# ETAG_v4.net
KiCad netlist of a schematic drawn in EAGLE
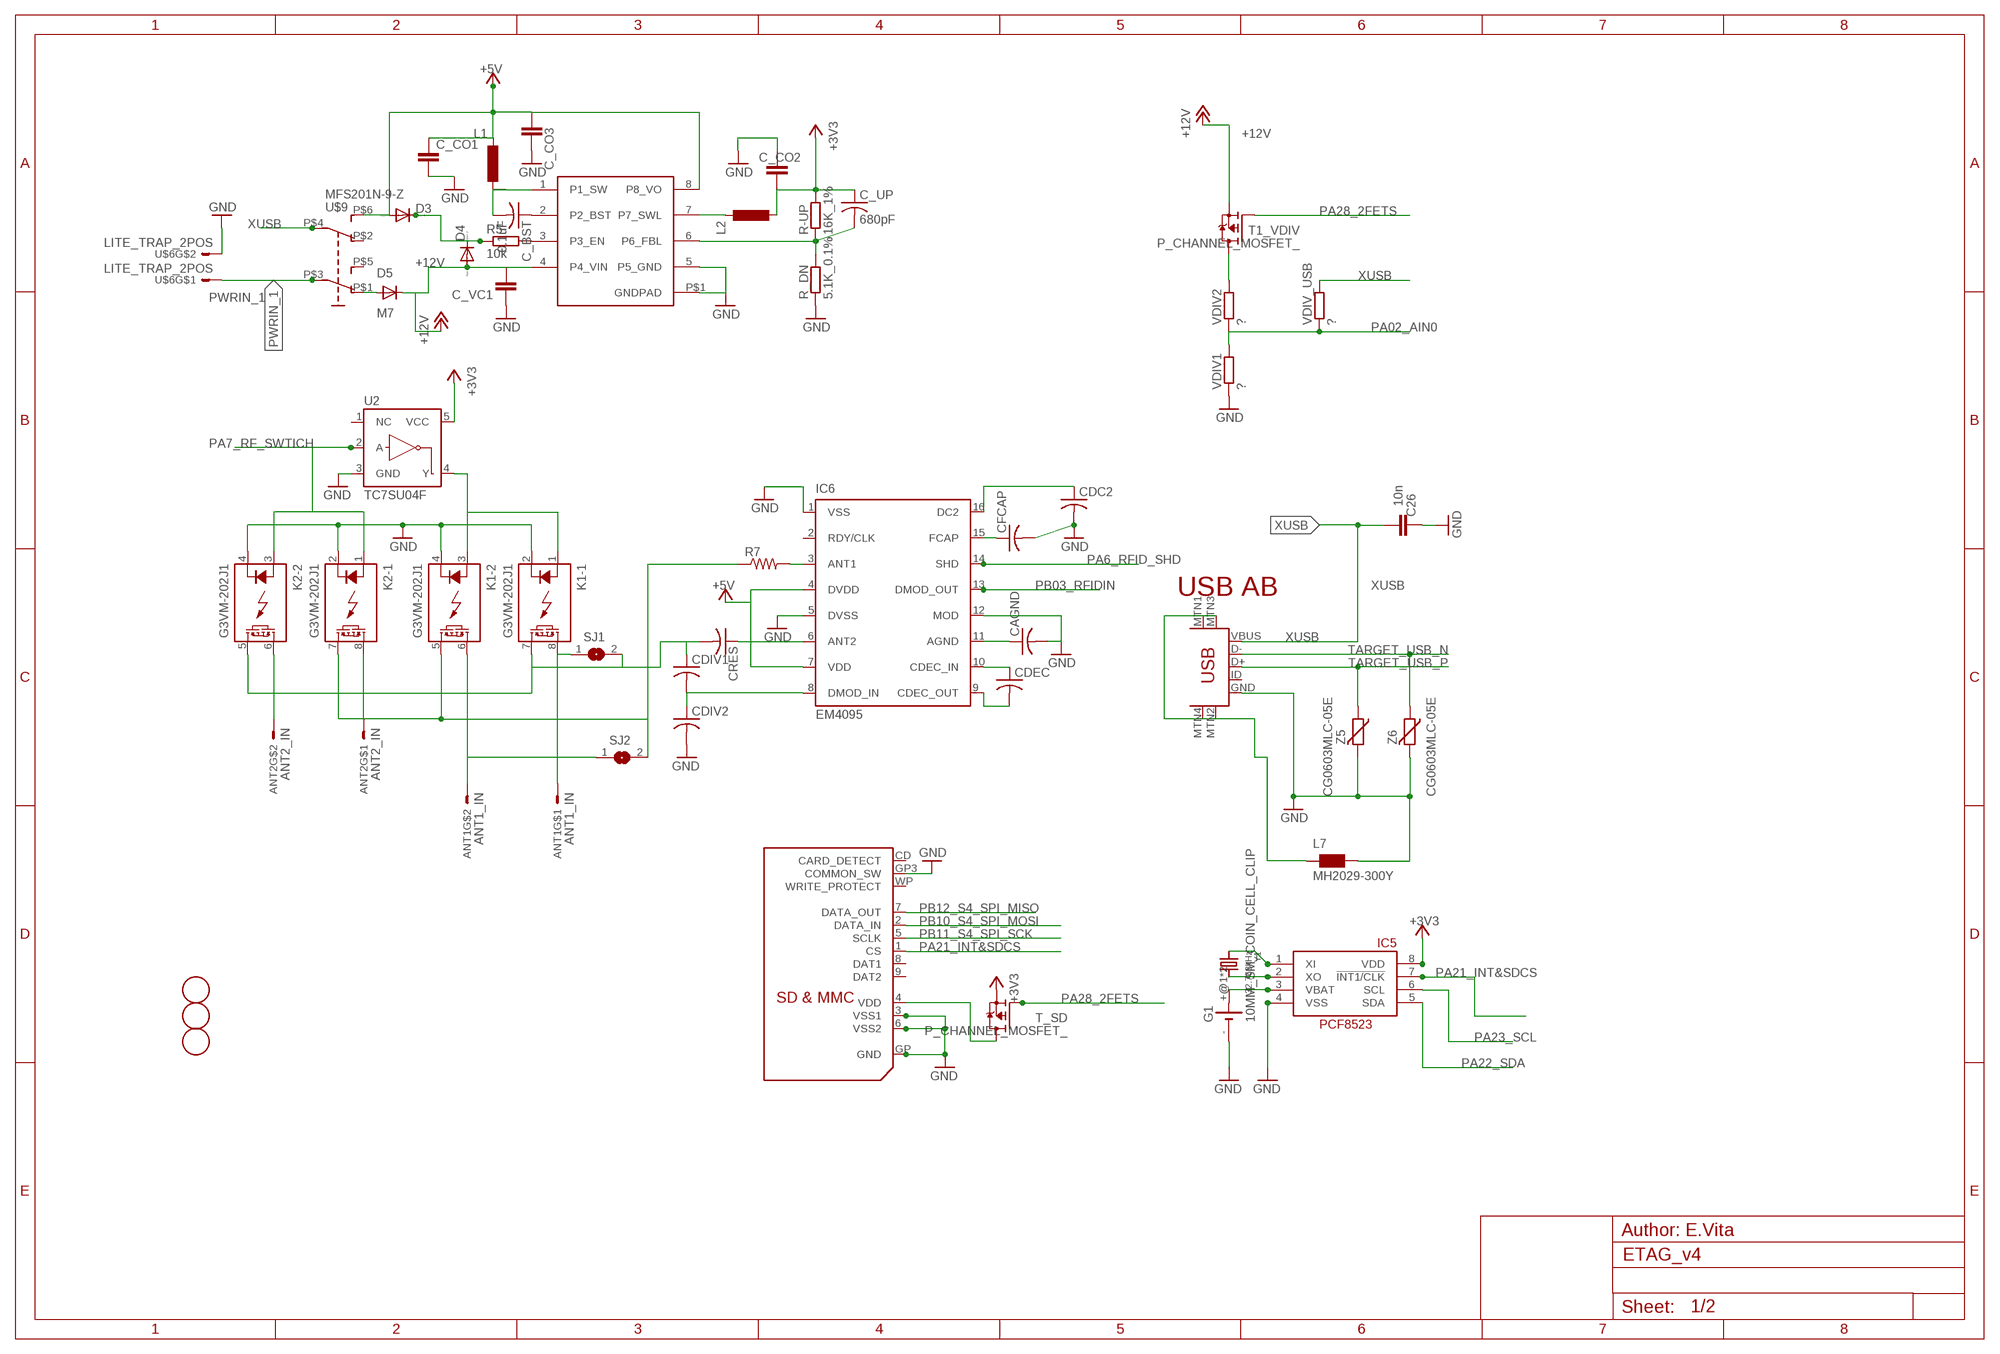
[diagram p0: schematic, sheet 1]
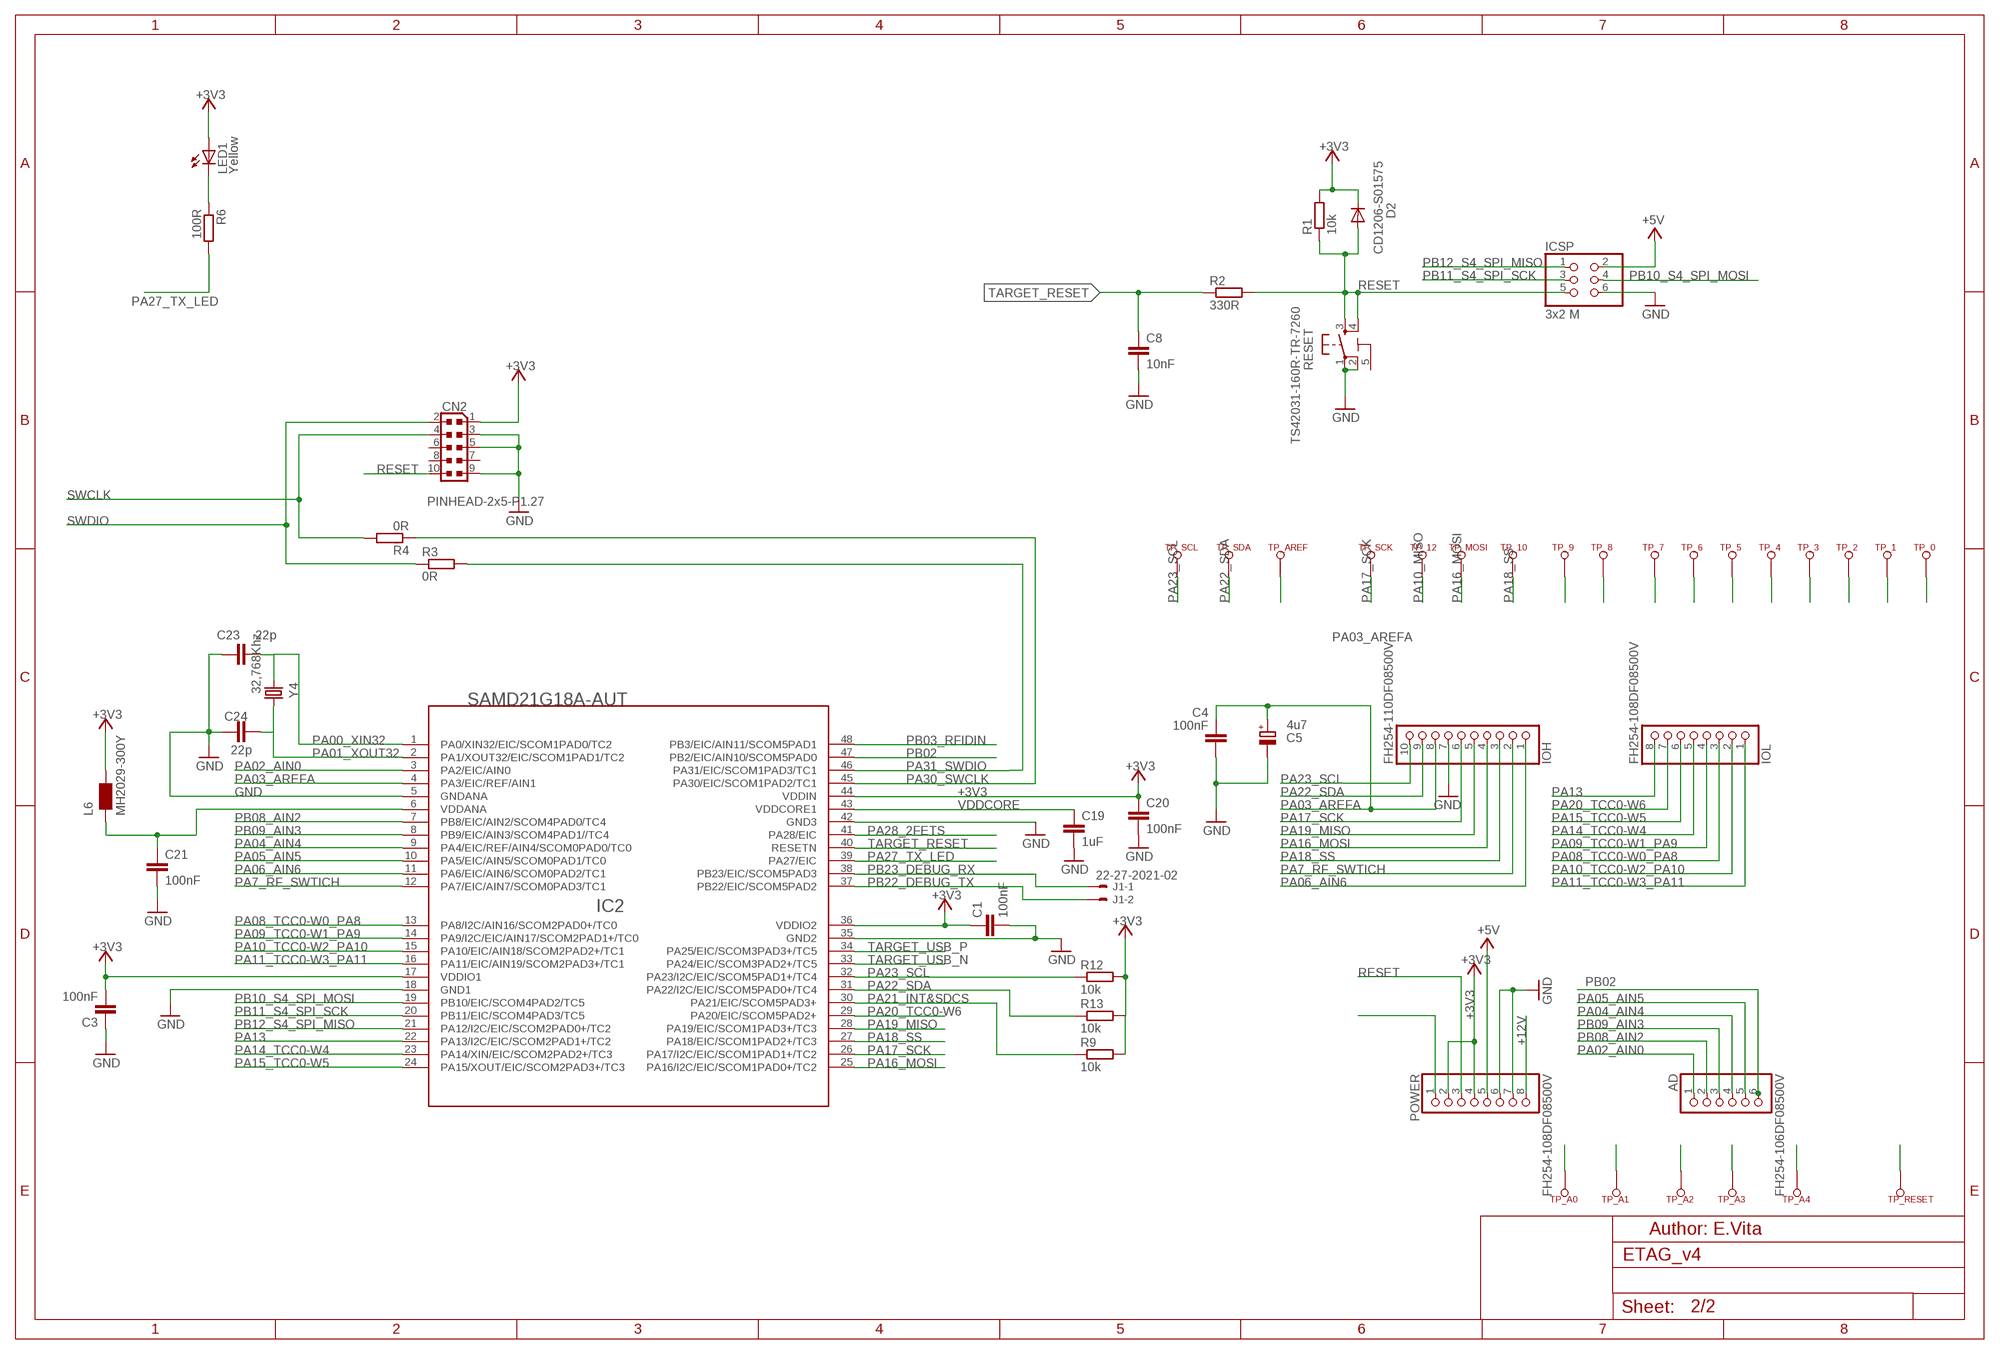
[diagram p1: schematic, sheet 2]

(export (version "E")
  (design (tool "Eeschema 10.0.6"))
  (components
    (comp (ref "AD")
      (value "FH254-106DF08500V")
      (footprint "eagle-import:1X06")
      (fields (field (name "PART_NUMBER") "20TW-535"))
      (libsource (lib "eagle-import") (part "1682_20TW-535_STD"))
    )
    (comp (ref "C1")
      (value "100nF")
      (footprint "eagle-import:C0603-ROUND")
      (fields (field (name "PART_NUMBER") "cl10b104kbnc"))
      (libsource (lib "eagle-import") (part "0015_100NF_0603"))
    )
    (comp (ref "C3")
      (value "100nF")
      (footprint "eagle-import:C0603-ROUND")
      (fields (field (name "PART_NUMBER") "cl10b104kbnc"))
      (libsource (lib "eagle-import") (part "0015_100NF_0603"))
    )
    (comp (ref "C4")
      (value "100nF")
      (footprint "eagle-import:C0603-ROUND")
      (fields (field (name "PART_NUMBER") "cl10b104kbnc"))
      (libsource (lib "eagle-import") (part "0015_100NF_0603"))
    )
    (comp (ref "C5")
      (value "4u7")
      (footprint "eagle-import:SMC_A")
      (fields (field (name "PART_NUMBER") "TAJA475M016RNJ"))
      (libsource (lib "eagle-import") (part "0474_TAJA475M016RNJ"))
    )
    (comp (ref "C8")
      (value "10nF")
      (footprint "eagle-import:C0603-ROUND")
      (fields (field (name "PART_NUMBER") "10nF_0603"))
      (libsource (lib "eagle-import") (part "0142_10NF_0603"))
    )
    (comp (ref "C19")
      (value "1uF")
      (footprint "eagle-import:C0603-ROUND")
      (fields (field (name "PART_NUMBER") "1uF_0603/GRM188R61E105KA12D"))
      (libsource (lib "eagle-import") (part "0006_1UF_0603/GRM188R61E105KA12D"))
    )
    (comp (ref "C20")
      (value "100nF")
      (footprint "eagle-import:C0603-ROUND")
      (fields (field (name "PART_NUMBER") "cl10b104kbnc"))
      (libsource (lib "eagle-import") (part "0015_100NF_0603"))
    )
    (comp (ref "C21")
      (value "100nF")
      (footprint "eagle-import:C0603-ROUND")
      (fields (field (name "PART_NUMBER") "cl10b104kbnc"))
      (libsource (lib "eagle-import") (part "0015_100NF_0603"))
    )
    (comp (ref "C23")
      (value "22p")
      (footprint "eagle-import:C0603-ROUND")
      (fields (field (name "PART_NUMBER") "22pF_0603"))
      (libsource (lib "eagle-import") (part "0014_22PF_0603"))
    )
    (comp (ref "C24")
      (value "22p")
      (footprint "eagle-import:C0603-ROUND")
      (fields (field (name "PART_NUMBER") "22pF_0603"))
      (libsource (lib "eagle-import") (part "0014_22PF_0603"))
    )
    (comp (ref "CN2")
      (value "PINHEAD-2x5-P1.27")
      (footprint "eagle-import:PINHEAD_2X05_127")
      (libsource (lib "eagle-import") (part "0171_PH127-205DF055G00AROUND-PADS"))
    )
    (comp (ref "D2")
      (value "CD1206-S01575")
      (footprint "eagle-import:MINIMELF")
      (libsource (lib "eagle-import") (part "0012_CD1206-S01575"))
    )
    (comp (ref "IC2")
      (value "SAMD21G18A-AUT")
      (footprint "eagle-import:TQFP48-7X7")
      (libsource (lib "eagle-import") (part "1792_SAMD21G18A-AUT"))
    )
    (comp (ref "ICSP")
      (value "3x2 M")
      (footprint "eagle-import:2X03")
      (fields (field (name "PART_NUMBER") "PH254-203DF118A00V"))
      (libsource (lib "eagle-import") (part "0114_PH254-203DF118A00V"))
    )
    (comp (ref "IOH")
      (value "FH254-110DF08500V")
      (footprint "eagle-import:1X10")
      (fields (field (name "PART_NUMBER") "20TW-537"))
      (libsource (lib "eagle-import") (part "1684_20TW-537"))
    )
    (comp (ref "IOL")
      (value "FH254-108DF08500V")
      (footprint "eagle-import:1X08")
      (fields (field (name "PART_NUMBER") "20TW-536"))
      (libsource (lib "eagle-import") (part "1683_20TW-536"))
    )
    (comp (ref "J1")
      (value "22-27-2021-02")
      (footprint "eagle-import:6410-02")
      (libsource (lib "eagle-import") (part "22-?-0227-2021"))
    )
    (comp (ref "L6")
      (value "MH2029-300Y")
      (footprint "eagle-import:0805")
      (fields (field (name "PART_NUMBER") "BLM21PG300SN1D_/_MH2029-300Y"))
      (libsource (lib "eagle-import") (part "0001_BLM21PG300SN1D_/_MH2029-300Y"))
    )
    (comp (ref "LED1")
      (value "Yellow")
      (footprint "eagle-import:CHIPLED_0805")
      (fields (field (name "PART_NUMBER") "KPT-2012YC"))
      (libsource (lib "eagle-import") (part "0044_KPT-2012YC"))
    )
    (comp (ref "POWER")
      (value "FH254-108DF08500V")
      (footprint "eagle-import:1X08")
      (fields (field (name "PART_NUMBER") "20TW-536"))
      (libsource (lib "eagle-import") (part "1683_20TW-536"))
    )
    (comp (ref "R1")
      (value "10k")
      (footprint "eagle-import:R0603-ROUND")
      (fields (field (name "PART_NUMBER") "CR0603JW103L"))
      (libsource (lib "eagle-import") (part "0028_CR0603JW103L"))
    )
    (comp (ref "R2")
      (value "330R")
      (footprint "eagle-import:R0603-ROUND")
      (fields (field (name "PART_NUMBER") "330R_0603"))
      (libsource (lib "eagle-import") (part "0049_330R_0603"))
    )
    (comp (ref "R3")
      (value "0R")
      (footprint "eagle-import:R0603-ROUND")
      (fields (field (name "PART_NUMBER") "0R_0603"))
      (libsource (lib "eagle-import") (part "0233_0R_0603"))
    )
    (comp (ref "R4")
      (value "0R")
      (footprint "eagle-import:R0603-ROUND")
      (fields (field (name "PART_NUMBER") "0R_0603"))
      (libsource (lib "eagle-import") (part "0233_0R_0603"))
    )
    (comp (ref "R6")
      (value "100R")
      (footprint "eagle-import:R0603-ROUND")
      (fields (field (name "PART_NUMBER") "0R_0603"))
      (libsource (lib "eagle-import") (part "0233_0R_0603"))
    )
    (comp (ref "R9")
      (value "10k")
      (footprint "eagle-import:R0603-ROUND")
      (fields (field (name "PART_NUMBER") "CR0603JW103L"))
      (libsource (lib "eagle-import") (part "0028_CR0603JW103L"))
    )
    (comp (ref "R12")
      (value "10k")
      (footprint "eagle-import:R0603-ROUND")
      (fields (field (name "PART_NUMBER") "CR0603JW103L"))
      (libsource (lib "eagle-import") (part "0028_CR0603JW103L"))
    )
    (comp (ref "R13")
      (value "10k")
      (footprint "eagle-import:R0603-ROUND")
      (fields (field (name "PART_NUMBER") "CR0603JW103L"))
      (libsource (lib "eagle-import") (part "0028_CR0603JW103L"))
    )
    (comp (ref "RESET")
      (value "TS42031-160R-TR-7260")
      (footprint "eagle-import:TS42")
      (fields (field (name "PART_NUMBER") "IT-1157AHNP-160G-G_GTR"))
      (libsource (lib "eagle-import") (part "0946_TS42031-160W-TR-7260"))
    )
    (comp (ref "TP_0")
      (value "TP_SP")
      (footprint "eagle-import:TP-SP")
      (libsource (lib "eagle-import") (part "TP_SP"))
    )
    (comp (ref "TP_1")
      (value "TP_SP")
      (footprint "eagle-import:TP-SP")
      (libsource (lib "eagle-import") (part "TP_SP"))
    )
    (comp (ref "TP_2")
      (value "TP_SP")
      (footprint "eagle-import:TP-SP")
      (libsource (lib "eagle-import") (part "TP_SP"))
    )
    (comp (ref "TP_3")
      (value "TP_SP")
      (footprint "eagle-import:TP-SP")
      (libsource (lib "eagle-import") (part "TP_SP"))
    )
    (comp (ref "TP_4")
      (value "TP_SP")
      (footprint "eagle-import:TP-SP")
      (libsource (lib "eagle-import") (part "TP_SP"))
    )
    (comp (ref "TP_5")
      (value "TP_SP")
      (footprint "eagle-import:TP-SP")
      (libsource (lib "eagle-import") (part "TP_SP"))
    )
    (comp (ref "TP_6")
      (value "TP_SP")
      (footprint "eagle-import:TP-SP")
      (libsource (lib "eagle-import") (part "TP_SP"))
    )
    (comp (ref "TP_7")
      (value "TP_SP")
      (footprint "eagle-import:TP-SP")
      (libsource (lib "eagle-import") (part "TP_SP"))
    )
    (comp (ref "TP_8")
      (value "TP_SP")
      (footprint "eagle-import:TP-SP")
      (libsource (lib "eagle-import") (part "TP_SP"))
    )
    (comp (ref "TP_9")
      (value "TP_SP")
      (footprint "eagle-import:TP-SP")
      (libsource (lib "eagle-import") (part "TP_SP"))
    )
    (comp (ref "TP_10")
      (value "TP_SP")
      (footprint "eagle-import:TP-SP")
      (libsource (lib "eagle-import") (part "TP_SP"))
    )
    (comp (ref "TP_12")
      (value "TP_SP")
      (footprint "eagle-import:TP-SP")
      (libsource (lib "eagle-import") (part "TP_SP"))
    )
    (comp (ref "TP_A0")
      (value "TP_SP")
      (footprint "eagle-import:TP-SP")
      (libsource (lib "eagle-import") (part "TP_SP"))
    )
    (comp (ref "TP_A1")
      (value "TP_SP")
      (footprint "eagle-import:TP-SP")
      (libsource (lib "eagle-import") (part "TP_SP"))
    )
    (comp (ref "TP_A2")
      (value "TP_SP")
      (footprint "eagle-import:TP-SP")
      (libsource (lib "eagle-import") (part "TP_SP"))
    )
    (comp (ref "TP_A3")
      (value "TP_SP")
      (footprint "eagle-import:TP-SP")
      (libsource (lib "eagle-import") (part "TP_SP"))
    )
    (comp (ref "TP_A4")
      (value "TP_SP")
      (footprint "eagle-import:TP-SP")
      (libsource (lib "eagle-import") (part "TP_SP"))
    )
    (comp (ref "TP_AREF")
      (value "TP_SP")
      (footprint "eagle-import:TP-SP")
      (libsource (lib "eagle-import") (part "TP_SP"))
    )
    (comp (ref "TP_MOSI")
      (value "TP_SP")
      (footprint "eagle-import:TP-SP")
      (libsource (lib "eagle-import") (part "TP_SP"))
    )
    (comp (ref "TP_RESET")
      (value "TP_SP")
      (footprint "eagle-import:TP-SP")
      (libsource (lib "eagle-import") (part "TP_SP"))
    )
    (comp (ref "TP_SCK")
      (value "TP_SP")
      (footprint "eagle-import:TP-SP")
      (libsource (lib "eagle-import") (part "TP_SP"))
    )
    (comp (ref "TP_SCL")
      (value "TP_SP")
      (footprint "eagle-import:TP-SP")
      (libsource (lib "eagle-import") (part "TP_SP"))
    )
    (comp (ref "TP_SDA")
      (value "TP_SP")
      (footprint "eagle-import:TP-SP")
      (libsource (lib "eagle-import") (part "TP_SP"))
    )
    (comp (ref "Y4")
      (value "32,768Khz")
      (footprint "eagle-import:RESONATOR_EPSON_FC_145")
      (fields (field (name "PART_NUMBER") "ABS07-32.768KHZ-T"))
      (libsource (lib "eagle-import") (part "0213_ABS07-32.768KHZ-T"))
    )
    (comp (ref "ANT1")
      (value "ANT1_IN")
      (footprint "eagle-import:LITE_TRAP_MINI")
      (libsource (lib "eagle-import") (part "LITE_TRAP_2POS"))
    )
    (comp (ref "ANT2")
      (value "ANT2_IN")
      (footprint "eagle-import:LITE_TRAP_MINI")
      (libsource (lib "eagle-import") (part "LITE_TRAP_2POS"))
    )
    (comp (ref "C26")
      (value "10n")
      (footprint "eagle-import:C0603-ROUND")
      (fields (field (name "PART_NUMBER") "10nF_0603"))
      (libsource (lib "eagle-import") (part "0142_10NF_0603"))
    )
    (comp (ref "CAGND")
      (value "C-US")
      (footprint "eagle-import:C0603-ROUND")
      (libsource (lib "eagle-import") (part "C-US"))
    )
    (comp (ref "CDC2")
      (value "C-US")
      (footprint "eagle-import:C0603-ROUND")
      (libsource (lib "eagle-import") (part "C-US"))
    )
    (comp (ref "CDEC")
      (value "C-US")
      (footprint "eagle-import:C0603-ROUND")
      (libsource (lib "eagle-import") (part "C-US"))
    )
    (comp (ref "CDIV1")
      (value "C-USC1206K")
      (footprint "eagle-import:C1206K")
      (libsource (lib "eagle-import") (part "C-USC1206K"))
    )
    (comp (ref "CDIV2")
      (value "C-USC1206K")
      (footprint "eagle-import:C1206K")
      (libsource (lib "eagle-import") (part "C-USC1206K"))
    )
    (comp (ref "CFCAP")
      (value "C-US")
      (footprint "eagle-import:C0603-ROUND")
      (libsource (lib "eagle-import") (part "C-US"))
    )
    (comp (ref "CRES")
      (value "C-USC1206K")
      (footprint "eagle-import:C1206K")
      (libsource (lib "eagle-import") (part "C-USC1206K"))
    )
    (comp (ref "C_BST")
      (value "0.1uF")
      (footprint "eagle-import:C0603-ROUND")
      (libsource (lib "eagle-import") (part "C-US"))
    )
    (comp (ref "C_CO1")
      (value "22uF")
      (footprint "eagle-import:C0805")
      (libsource (lib "eagle-import") (part "C-EUC0805"))
    )
    (comp (ref "C_CO2")
      (value "22uF")
      (footprint "eagle-import:C0805")
      (libsource (lib "eagle-import") (part "C-EUC0805"))
    )
    (comp (ref "C_CO3")
      (value "10uF")
      (footprint "eagle-import:C0805")
      (libsource (lib "eagle-import") (part "C-EUC0805"))
    )
    (comp (ref "C_UP")
      (value "680pF")
      (footprint "eagle-import:C0603-ROUND")
      (libsource (lib "eagle-import") (part "C-US"))
    )
    (comp (ref "C_VC1")
      (value "10uF")
      (footprint "eagle-import:C1210")
      (libsource (lib "eagle-import") (part "C-EUC1210"))
    )
    (comp (ref "D3")
      (value "DIODE-LL-34")
      (footprint "eagle-import:LL-34")
      (libsource (lib "eagle-import") (part "DIODE-LL-34"))
    )
    (comp (ref "D4")
      (value "DIODE-LL-34")
      (footprint "eagle-import:LL-34")
      (libsource (lib "eagle-import") (part "DIODE-LL-34"))
    )
    (comp (ref "D5")
      (value "M7")
      (footprint "eagle-import:SMB")
      (libsource (lib "eagle-import") (part "0020_M7"))
    )
    (comp (ref "FD1")
      (value "FIDUCIALMOUNT")
      (footprint "eagle-import:FIDUCIA-MOUNT")
      (libsource (lib "eagle-import") (part "FIDUCIALMOUNT"))
    )
    (comp (ref "FD2")
      (value "FIDUCIALMOUNT")
      (footprint "eagle-import:FIDUCIA-MOUNT")
      (libsource (lib "eagle-import") (part "FIDUCIALMOUNT"))
    )
    (comp (ref "FD3")
      (value "FIDUCIALMOUNT")
      (footprint "eagle-import:FIDUCIA-MOUNT")
      (libsource (lib "eagle-import") (part "FIDUCIALMOUNT"))
    )
    (comp (ref "G1")
      (value "10MM_SM_COIN_CELL_CLIP")
      (footprint "eagle-import:10MM_SM_COIN_CELL_CLIP")
      (libsource (lib "eagle-import") (part "10MM_SM_COIN_CELL_CLIP"))
    )
    (comp (ref "IC5")
      (value "RTC_PCF8523T")
      (footprint "eagle-import:SOIC8_150MIL")
      (libsource (lib "eagle-import") (part "RTC_PCF8523T"))
    )
    (comp (ref "IC6")
      (value "EM4095")
      (footprint "eagle-import:SO16")
      (libsource (lib "eagle-import") (part "EM4095"))
    )
    (comp (ref "K1")
      (value "G3VM-202J1")
      (footprint "eagle-import:SOP08")
      (libsource (lib "eagle-import") (part "AQWSOP21"))
    )
    (comp (ref "K2")
      (value "G3VM-202J1")
      (footprint "eagle-import:SOP08")
      (libsource (lib "eagle-import") (part "AQWSOP21"))
    )
    (comp (ref "L1")
      (value "22uH")
      (footprint "eagle-import:SLF10165")
      (libsource (lib "eagle-import") (part "L-EUSLF_10MM"))
    )
    (comp (ref "L2")
      (value "2.2uH")
      (footprint "eagle-import:L1008(2520METRIC)")
      (libsource (lib "eagle-import") (part "L-EU1008"))
    )
    (comp (ref "L7")
      (value "MH2029-300Y")
      (footprint "eagle-import:0805")
      (fields (field (name "PART_NUMBER") "BLM21PG300SN1D_/_MH2029-300Y"))
      (libsource (lib "eagle-import") (part "0001_BLM21PG300SN1D_/_MH2029-300Y"))
    )
    (comp (ref "R-UP")
      (value "16K_1%")
      (footprint "eagle-import:R0603-ROUND")
      (fields (field (name "PART_NUMBER") "CR0603FW104L"))
      (libsource (lib "eagle-import") (part "2022_CR0603FW104L"))
    )
    (comp (ref "R5")
      (value "10k")
      (footprint "eagle-import:R0603-ROUND")
      (fields (field (name "PART_NUMBER") "CR0603JW103L"))
      (libsource (lib "eagle-import") (part "0028_CR0603JW103L"))
    )
    (comp (ref "R7")
      (value "R-US_R1206")
      (footprint "eagle-import:R1206")
      (libsource (lib "eagle-import") (part "R-US_R1206"))
    )
    (comp (ref "R_DN")
      (value "5.1K_0.1%")
      (footprint "eagle-import:R0603-ROUND")
      (libsource (lib "eagle-import") (part "2339_"))
    )
    (comp (ref "SJ1")
      (value "SJW")
      (footprint "eagle-import:SJW")
      (libsource (lib "eagle-import") (part "SJW"))
    )
    (comp (ref "SJ2")
      (value "SJW")
      (footprint "eagle-import:SJW")
      (libsource (lib "eagle-import") (part "SJW"))
    )
    (comp (ref "T1_VDIV")
      (value "P_CHANNEL_MOSFET_")
      (footprint "eagle-import:SOT23")
      (libsource (lib "eagle-import") (part "P_CHANNEL_MOSFET_"))
    )
    (comp (ref "T_SD")
      (value "P_CHANNEL_MOSFET_")
      (footprint "eagle-import:SOT23")
      (libsource (lib "eagle-import") (part "P_CHANNEL_MOSFET_"))
    )
    (comp (ref "U$3")
      (value "BD93291EFJSOP8_W_GND")
      (footprint "eagle-import:SOP08_GNDPAD")
      (libsource (lib "eagle-import") (part "BD93291EFJSOP8_W_GND"))
    )
    (comp (ref "U$4")
      (value "SDMMC06132")
      (footprint "eagle-import:06132")
      (libsource (lib "eagle-import") (part "SDMMC06132"))
    )
    (comp (ref "U$5")
      (value "USB-MINIB-5PIN")
      (footprint "eagle-import:USB-MINIB")
      (libsource (lib "eagle-import") (part "USB-MINIB-5PIN"))
    )
    (comp (ref "U$6")
      (value "LITE_TRAP_2POS")
      (footprint "eagle-import:LITE_TRAP_MINI")
      (libsource (lib "eagle-import") (part "LITE_TRAP_2POS"))
    )
    (comp (ref "U$9")
      (value "MFS201N-9-Z")
      (footprint "eagle-import:MFS201N-9-Z")
      (libsource (lib "eagle-import") (part "MFS201N-9-Z"))
    )
    (comp (ref "U2")
      (value "TC7SU04F")
      (footprint "eagle-import:SOT23-5")
      (libsource (lib "eagle-import") (part "INVERTER_SOT23-5"))
    )
    (comp (ref "VDIV1")
      (value "?")
      (footprint "eagle-import:R0603-ROUND")
      (libsource (lib "eagle-import") (part "2339_"))
    )
    (comp (ref "VDIV2")
      (value "?")
      (footprint "eagle-import:R0603-ROUND")
      (fields (field (name "PART_NUMBER") "CR0603FW104L"))
      (libsource (lib "eagle-import") (part "2022_CR0603FW104L"))
    )
    (comp (ref "VDIV_USB")
      (value "?")
      (footprint "eagle-import:R0603-ROUND")
      (libsource (lib "eagle-import") (part "2339_"))
    )
    (comp (ref "Y1")
      (value "32.768kHz")
      (footprint "eagle-import:CRYSTAL_8X3.8")
      (libsource (lib "eagle-import") (part "CRYSTAL8.0X3.8"))
    )
    (comp (ref "Z5")
      (value "CG0603MLC-05E")
      (footprint "eagle-import:CT_CN0603")
      (fields (field (name "PART_NUMBER") "BRNCG0603MLC-05E"))
      (libsource (lib "eagle-import") (part "0010_BRNCG0603MLC-05E"))
    )
    (comp (ref "Z6")
      (value "CG0603MLC-05E")
      (footprint "eagle-import:CT_CN0603")
      (fields (field (name "PART_NUMBER") "BRNCG0603MLC-05E"))
      (libsource (lib "eagle-import") (part "0010_BRNCG0603MLC-05E"))
    )
  )
  (nets
    (net (code "1") (name "+3V3") (class "Default")
      (node (ref "C1") (pin "1") (pinfunction "1_1") (pintype "passive"))
      (node (ref "C20") (pin "1") (pinfunction "1_1") (pintype "passive"))
      (node (ref "C3") (pin "2") (pinfunction "2_2") (pintype "passive"))
      (node (ref "CN2") (pin "1") (pinfunction "1_1") (pintype "passive"))
      (node (ref "C_CO2") (pin "2") (pinfunction "2_2") (pintype "passive"))
      (node (ref "C_UP") (pin "1") (pinfunction "1_1") (pintype "passive"))
      (node (ref "D2") (pin "C") (pinfunction "C_C") (pintype "passive"))
      (node (ref "IC2") (pin "17") (pinfunction "VDDIO1_17") (pintype "power_in"))
      (node (ref "IC2") (pin "36") (pinfunction "VDDIO2_36") (pintype "power_in"))
      (node (ref "IC2") (pin "44") (pinfunction "VDDIN_44") (pintype "power_in"))
      (node (ref "IC5") (pin "8") (pinfunction "VDD_8") (pintype "power_in"))
      (node (ref "L2") (pin "2") (pinfunction "2_2") (pintype "passive"))
      (node (ref "L6") (pin "2") (pinfunction "2_2") (pintype "passive"))
      (node (ref "LED1") (pin "A") (pinfunction "A_A") (pintype "passive"))
      (node (ref "POWER") (pin "2") (pinfunction "2_2") (pintype "passive"))
      (node (ref "POWER") (pin "4") (pinfunction "4_4") (pintype "passive"))
      (node (ref "R-UP") (pin "2") (pinfunction "2_2") (pintype "passive"))
      (node (ref "R1") (pin "2") (pinfunction "2_2") (pintype "passive"))
      (node (ref "R12") (pin "2") (pinfunction "2_2") (pintype "passive"))
      (node (ref "R13") (pin "2") (pinfunction "2_2") (pintype "passive"))
      (node (ref "R9") (pin "2") (pinfunction "2_2") (pintype "passive"))
      (node (ref "T_SD") (pin "2") (pinfunction "S_2") (pintype "passive"))
      (node (ref "U2") (pin "5") (pinfunction "VCC_5") (pintype "bidirectional"))
    )
    (net (code "2") (name "+5V") (class "Default")
      (node (ref "C_CO1") (pin "1") (pinfunction "1_1") (pintype "passive"))
      (node (ref "C_CO3") (pin "1") (pinfunction "1_1") (pintype "passive"))
      (node (ref "D3") (pin "P$1") (pinfunction "A_P$1") (pintype "passive"))
      (node (ref "IC6") (pin "4") (pinfunction "DVDD_4") (pintype "power_in"))
      (node (ref "IC6") (pin "7") (pinfunction "VDD_7") (pintype "power_in"))
      (node (ref "ICSP") (pin "2") (pinfunction "2_2") (pintype "passive"))
      (node (ref "L1") (pin "P$1") (pinfunction "1_P$1") (pintype "passive"))
      (node (ref "POWER") (pin "5") (pinfunction "5_5") (pintype "passive"))
      (node (ref "U$3") (pin "8") (pinfunction "P8_VO_8") (pintype "bidirectional"))
      (node (ref "U$9") (pin "P$6") (pinfunction "S1_P$6") (pintype "passive"))
    )
    (net (code "3") (name "+12V") (class "Default")
      (node (ref "C_VC1") (pin "2") (pinfunction "2_2") (pintype "passive"))
      (node (ref "D4") (pin "P$1") (pinfunction "A_P$1") (pintype "passive"))
      (node (ref "D5") (pin "C") (pinfunction "C_C") (pintype "passive"))
      (node (ref "POWER") (pin "8") (pinfunction "8_8") (pintype "passive"))
      (node (ref "T1_VDIV") (pin "2") (pinfunction "S_2") (pintype "passive"))
      (node (ref "U$3") (pin "4") (pinfunction "P4_VIN_4") (pintype "bidirectional"))
    )
    (net (code "4") (name "5-GND") (class "Default")
      (node (ref "RESET") (pin "5") (pinfunction "5-GND_5") (pintype "power_in"))
    )
    (net (code "5") (name "GND") (class "Default")
      (node (ref "C1") (pin "2") (pinfunction "2_2") (pintype "passive"))
      (node (ref "C19") (pin "2") (pinfunction "2_2") (pintype "passive"))
      (node (ref "C20") (pin "2") (pinfunction "2_2") (pintype "passive"))
      (node (ref "C21") (pin "2") (pinfunction "2_2") (pintype "passive"))
      (node (ref "C23") (pin "1") (pinfunction "1_1") (pintype "passive"))
      (node (ref "C24") (pin "1") (pinfunction "1_1") (pintype "passive"))
      (node (ref "C26") (pin "2") (pinfunction "2_2") (pintype "passive"))
      (node (ref "C3") (pin "1") (pinfunction "1_1") (pintype "passive"))
      (node (ref "C4") (pin "2") (pinfunction "2_2") (pintype "passive"))
      (node (ref "C5") (pin "-") (pinfunction "-_-") (pintype "passive"))
      (node (ref "C8") (pin "2") (pinfunction "2_2") (pintype "passive"))
      (node (ref "CAGND") (pin "2") (pinfunction "2_2") (pintype "passive"))
      (node (ref "CDC2") (pin "2") (pinfunction "2_2") (pintype "passive"))
      (node (ref "CDIV2") (pin "2") (pinfunction "2_2") (pintype "passive"))
      (node (ref "CFCAP") (pin "2") (pinfunction "2_2") (pintype "passive"))
      (node (ref "CN2") (pin "3") (pinfunction "3_3") (pintype "passive"))
      (node (ref "CN2") (pin "5") (pinfunction "5_5") (pintype "passive"))
      (node (ref "CN2") (pin "9") (pinfunction "9_9") (pintype "passive"))
      (node (ref "C_CO1") (pin "2") (pinfunction "2_2") (pintype "passive"))
      (node (ref "C_CO2") (pin "1") (pinfunction "1_1") (pintype "passive"))
      (node (ref "C_CO3") (pin "2") (pinfunction "2_2") (pintype "passive"))
      (node (ref "C_VC1") (pin "1") (pinfunction "1_1") (pintype "passive"))
      (node (ref "G1") (pin "-") (pinfunction "-_-") (pintype "passive"))
      (node (ref "IC2") (pin "18") (pinfunction "GND1_18") (pintype "power_in"))
      (node (ref "IC2") (pin "35") (pinfunction "GND2_35") (pintype "power_in"))
      (node (ref "IC2") (pin "42") (pinfunction "GND3_42") (pintype "power_in"))
      (node (ref "IC2") (pin "5") (pinfunction "GNDANA_5") (pintype "power_in"))
      (node (ref "IC5") (pin "4") (pinfunction "VSS_4") (pintype "power_in"))
      (node (ref "IC6") (pin "1") (pinfunction "VSS_1") (pintype "power_in"))
      (node (ref "IC6") (pin "12") (pinfunction "MOD_12") (pintype "input"))
      (node (ref "IC6") (pin "5") (pinfunction "DVSS_5") (pintype "power_in"))
      (node (ref "ICSP") (pin "6") (pinfunction "6_6") (pintype "passive"))
      (node (ref "IOH") (pin "7") (pinfunction "7_7") (pintype "passive"))
      (node (ref "K1") (pin "2") (pinfunction "K_2") (pintype "passive"))
      (node (ref "K1") (pin "4") (pinfunction "K_4") (pintype "passive"))
      (node (ref "K2") (pin "2") (pinfunction "K_2") (pintype "passive"))
      (node (ref "K2") (pin "4") (pinfunction "K_4") (pintype "passive"))
      (node (ref "L7") (pin "2") (pinfunction "2_2") (pintype "passive"))
      (node (ref "POWER") (pin "6") (pinfunction "6_6") (pintype "passive"))
      (node (ref "POWER") (pin "7") (pinfunction "7_7") (pintype "passive"))
      (node (ref "RESET") (pin "1") (pinfunction "1_1") (pintype "passive"))
      (node (ref "RESET") (pin "2") (pinfunction "2_2") (pintype "passive"))
      (node (ref "R_DN") (pin "1") (pinfunction "1_1") (pintype "passive"))
      (node (ref "U$3") (pin "5") (pinfunction "P5_GND_5") (pintype "bidirectional"))
      (node (ref "U$3") (pin "P$1") (pinfunction "GNDPAD_P$1") (pintype "bidirectional"))
      (node (ref "U$4") (pin "3") (pinfunction "VSS1_3") (pintype "power_in"))
      (node (ref "U$4") (pin "6") (pinfunction "VSS2_6") (pintype "power_in"))
      (node (ref "U$4") (pin "GP") (pinfunction "GND_GP") (pintype "power_in"))
      (node (ref "U$4") (pin "GP3") (pinfunction "COMMON_SW_GP3") (pintype "passive"))
      (node (ref "U$5") (pin "GND") (pinfunction "GND_GND") (pintype "bidirectional"))
      (node (ref "U$6") (pin "P$3") (pinfunction "S_P$3") (pintype "passive"))
      (node (ref "U$6") (pin "P$4") (pinfunction "S_P$4") (pintype "passive"))
      (node (ref "U2") (pin "3") (pinfunction "GND_3") (pintype "bidirectional"))
      (node (ref "VDIV1") (pin "1") (pinfunction "1_1") (pintype "passive"))
      (node (ref "Z5") (pin "2") (pinfunction "2_2") (pintype "passive"))
      (node (ref "Z6") (pin "2") (pinfunction "2_2") (pintype "passive"))
    )
    (net (code "6") (name "Net-(D3-C)") (class "Default")
      (node (ref "D3") (pin "P$2") (pinfunction "C_P$2") (pintype "passive"))
      (node (ref "D4") (pin "P$2") (pinfunction "C_P$2") (pintype "passive"))
      (node (ref "R5") (pin "1") (pinfunction "1_1") (pintype "passive"))
    )
    (net (code "7") (name "Net-(IC2-VDDANA)") (class "Default")
      (node (ref "C21") (pin "1") (pinfunction "1_1") (pintype "passive"))
      (node (ref "IC2") (pin "6") (pinfunction "VDDANA_6") (pintype "power_in"))
      (node (ref "L6") (pin "1") (pinfunction "1_1") (pintype "passive"))
    )
    (net (code "8") (name "Net-(IC5-VBAT)") (class "Default")
      (node (ref "G1") (pin "+@1") (pinfunction "+_+@1") (pintype "passive"))
      (node (ref "G1") (pin "+@2") (pinfunction "+_+@2") (pintype "passive"))
      (node (ref "IC5") (pin "3") (pinfunction "VBAT_3") (pintype "power_in"))
    )
    (net (code "9") (name "Net-(IC5-XI)") (class "Default")
      (node (ref "IC5") (pin "1") (pinfunction "XI_1") (pintype "input"))
      (node (ref "Y1") (pin "P$1") (pinfunction "1_P$1") (pintype "passive"))
    )
    (net (code "10") (name "Net-(IC5-XO)") (class "Default")
      (node (ref "IC5") (pin "2") (pinfunction "XO_2") (pintype "output"))
      (node (ref "Y1") (pin "P$4") (pinfunction "2_P$4") (pintype "passive"))
    )
    (net (code "11") (name "Net-(IC6-AGND)") (class "Default")
      (node (ref "CAGND") (pin "1") (pinfunction "1_1") (pintype "passive"))
      (node (ref "IC6") (pin "11") (pinfunction "AGND_11") (pintype "power_in"))
    )
    (net (code "12") (name "Net-(IC6-ANT1)") (class "Default")
      (node (ref "IC6") (pin "3") (pinfunction "ANT1_3") (pintype "passive"))
      (node (ref "R7") (pin "2") (pinfunction "2_2") (pintype "passive"))
    )
    (net (code "13") (name "Net-(IC6-ANT2)") (class "Default")
      (node (ref "CRES") (pin "1") (pinfunction "1_1") (pintype "passive"))
      (node (ref "IC6") (pin "6") (pinfunction "ANT2_6") (pintype "passive"))
    )
    (net (code "14") (name "Net-(IC6-CDEC_IN)") (class "Default")
      (node (ref "CDEC") (pin "1") (pinfunction "1_1") (pintype "passive"))
      (node (ref "IC6") (pin "10") (pinfunction "CDEC_IN_10") (pintype "input"))
    )
    (net (code "15") (name "Net-(IC6-CDEC_OUT)") (class "Default")
      (node (ref "CDEC") (pin "2") (pinfunction "2_2") (pintype "passive"))
      (node (ref "IC6") (pin "9") (pinfunction "CDEC_OUT_9") (pintype "output"))
    )
    (net (code "16") (name "Net-(IC6-DC2)") (class "Default")
      (node (ref "CDC2") (pin "1") (pinfunction "1_1") (pintype "passive"))
      (node (ref "IC6") (pin "16") (pinfunction "DC2_16") (pintype "passive"))
    )
    (net (code "17") (name "Net-(IC6-DMOD_IN)") (class "Default")
      (node (ref "CDIV1") (pin "2") (pinfunction "2_2") (pintype "passive"))
      (node (ref "CDIV2") (pin "1") (pinfunction "1_1") (pintype "passive"))
      (node (ref "IC6") (pin "8") (pinfunction "DMOD_IN_8") (pintype "input"))
    )
    (net (code "18") (name "Net-(IC6-FCAP)") (class "Default")
      (node (ref "CFCAP") (pin "1") (pinfunction "1_1") (pintype "passive"))
      (node (ref "IC6") (pin "15") (pinfunction "FCAP_15") (pintype "passive"))
    )
    (net (code "19") (name "Net-(K1A-A)") (class "Default")
      (node (ref "K1") (pin "1") (pinfunction "A_1") (pintype "passive"))
      (node (ref "K1") (pin "3") (pinfunction "A_3") (pintype "passive"))
      (node (ref "U2") (pin "4") (pinfunction "Y_4") (pintype "bidirectional"))
    )
    (net (code "20") (name "Net-(K1A-D1)") (class "Default")
      (node (ref "ANT1") (pin "P$1") (pinfunction "S_P$1") (pintype "passive"))
      (node (ref "ANT1") (pin "P$2") (pinfunction "S_P$2") (pintype "passive"))
      (node (ref "K1") (pin "8") (pinfunction "D1_8") (pintype "passive"))
      (node (ref "SJ1") (pin "1") (pinfunction "1_1") (pintype "passive"))
    )
    (net (code "21") (name "Net-(K1A-D2)") (class "Default")
      (node (ref "CDIV1") (pin "1") (pinfunction "1_1") (pintype "passive"))
      (node (ref "CRES") (pin "2") (pinfunction "2_2") (pintype "passive"))
      (node (ref "K1") (pin "7") (pinfunction "D2_7") (pintype "passive"))
      (node (ref "K2") (pin "5") (pinfunction "D2_5") (pintype "passive"))
      (node (ref "SJ1") (pin "2") (pinfunction "2_2") (pintype "passive"))
    )
    (net (code "22") (name "Net-(K1B-D1)") (class "Default")
      (node (ref "ANT1") (pin "P$3") (pinfunction "S_P$3") (pintype "passive"))
      (node (ref "ANT1") (pin "P$4") (pinfunction "S_P$4") (pintype "passive"))
      (node (ref "K1") (pin "6") (pinfunction "D1_6") (pintype "passive"))
      (node (ref "SJ2") (pin "1") (pinfunction "1_1") (pintype "passive"))
    )
    (net (code "23") (name "Net-(K1B-D2)") (class "Default")
      (node (ref "K1") (pin "5") (pinfunction "D2_5") (pintype "passive"))
      (node (ref "K2") (pin "7") (pinfunction "D2_7") (pintype "passive"))
      (node (ref "R7") (pin "1") (pinfunction "1_1") (pintype "passive"))
      (node (ref "SJ2") (pin "2") (pinfunction "2_2") (pintype "passive"))
    )
    (net (code "24") (name "Net-(K2A-D1)") (class "Default")
      (node (ref "ANT2") (pin "P$1") (pinfunction "S_P$1") (pintype "passive"))
      (node (ref "ANT2") (pin "P$2") (pinfunction "S_P$2") (pintype "passive"))
      (node (ref "K2") (pin "8") (pinfunction "D1_8") (pintype "passive"))
    )
    (net (code "25") (name "Net-(K2B-D1)") (class "Default")
      (node (ref "ANT2") (pin "P$3") (pinfunction "S_P$3") (pintype "passive"))
      (node (ref "ANT2") (pin "P$4") (pinfunction "S_P$4") (pintype "passive"))
      (node (ref "K2") (pin "6") (pinfunction "D1_6") (pintype "passive"))
    )
    (net (code "26") (name "Net-(L1-2)") (class "Default")
      (node (ref "C_BST") (pin "2") (pinfunction "2_2") (pintype "passive"))
      (node (ref "L1") (pin "P$2") (pinfunction "2_P$2") (pintype "passive"))
      (node (ref "U$3") (pin "1") (pinfunction "P1_SW_1") (pintype "bidirectional"))
    )
    (net (code "27") (name "Net-(LED1-PadC)") (class "Default")
      (node (ref "LED1") (pin "C") (pinfunction "C_C") (pintype "passive"))
      (node (ref "R6") (pin "1") (pinfunction "1_1") (pintype "passive"))
    )
    (net (code "28") (name "Net-(T1_VDIV-D)") (class "Default")
      (node (ref "T1_VDIV") (pin "3") (pinfunction "D_3") (pintype "passive"))
      (node (ref "VDIV2") (pin "2") (pinfunction "2_2") (pintype "passive"))
    )
    (net (code "29") (name "Net-(T_SD-D)") (class "Default")
      (node (ref "T_SD") (pin "3") (pinfunction "D_3") (pintype "passive"))
      (node (ref "U$4") (pin "4") (pinfunction "VDD_4") (pintype "power_in"))
    )
    (net (code "30") (name "Net-(U$3-P2_BST)") (class "Default")
      (node (ref "C_BST") (pin "1") (pinfunction "1_1") (pintype "passive"))
      (node (ref "U$3") (pin "2") (pinfunction "P2_BST_2") (pintype "bidirectional"))
    )
    (net (code "31") (name "Net-(U$3-P3_EN)") (class "Default")
      (node (ref "R5") (pin "2") (pinfunction "2_2") (pintype "passive"))
      (node (ref "U$3") (pin "3") (pinfunction "P3_EN_3") (pintype "bidirectional"))
    )
    (net (code "32") (name "Net-(U$3-P6_FBL)") (class "Default")
      (node (ref "C_UP") (pin "2") (pinfunction "2_2") (pintype "passive"))
      (node (ref "R-UP") (pin "1") (pinfunction "1_1") (pintype "passive"))
      (node (ref "R_DN") (pin "2") (pinfunction "2_2") (pintype "passive"))
      (node (ref "U$3") (pin "6") (pinfunction "P6_FBL_6") (pintype "bidirectional"))
    )
    (net (code "33") (name "Net-(U$3-P7_SWL)") (class "Default")
      (node (ref "L2") (pin "1") (pinfunction "1_1") (pintype "passive"))
      (node (ref "U$3") (pin "7") (pinfunction "P7_SWL_7") (pintype "bidirectional"))
    )
    (net (code "34") (name "Net-(U$5-MTN1)") (class "Default")
      (node (ref "L7") (pin "1") (pinfunction "1_1") (pintype "passive"))
      (node (ref "U$5") (pin "MTN1") (pinfunction "MTN2_MTN1") (pintype "bidirectional"))
      (node (ref "U$5") (pin "MTN2") (pinfunction "MTN3_MTN2") (pintype "bidirectional"))
      (node (ref "U$5") (pin "MTN3") (pinfunction "MTN1_MTN3") (pintype "bidirectional"))
      (node (ref "U$5") (pin "MTN4") (pinfunction "MTN4_MTN4") (pintype "bidirectional"))
    )
    (net (code "35") (name "Net-(U$9-O)") (class "Default")
      (node (ref "D5") (pin "A") (pinfunction "A_A") (pintype "passive"))
      (node (ref "U$9") (pin "P$1") (pinfunction "O_P$1") (pintype "passive"))
    )
    (net (code "36") (name "PA00_XIN32") (class "Default")
      (node (ref "C23") (pin "2") (pinfunction "2_2") (pintype "passive"))
      (node (ref "IC2") (pin "1") (pinfunction "PA0/XIN32/EIC/SCOM1PAD0/TC2_1") (pintype "bidirectional"))
      (node (ref "Y4") (pin "P$1") (pinfunction "1_P$1") (pintype "bidirectional"))
    )
    (net (code "37") (name "PA01_XOUT32") (class "Default")
      (node (ref "C24") (pin "2") (pinfunction "2_2") (pintype "passive"))
      (node (ref "IC2") (pin "2") (pinfunction "PA1/XOUT32/EIC/SCOM1PAD1/TC2_2") (pintype "bidirectional"))
      (node (ref "Y4") (pin "P$2") (pinfunction "2_P$2") (pintype "bidirectional"))
    )
    (net (code "38") (name "PA02_AIN0") (class "Default")
      (node (ref "AD") (pin "1") (pinfunction "1_1") (pintype "passive"))
      (node (ref "IC2") (pin "3") (pinfunction "PA2/EIC/AIN0_3") (pintype "bidirectional"))
      (node (ref "TP_A0") (pin "X") (pinfunction "TESTP_X") (pintype "passive"))
      (node (ref "VDIV1") (pin "2") (pinfunction "2_2") (pintype "passive"))
      (node (ref "VDIV2") (pin "1") (pinfunction "1_1") (pintype "passive"))
      (node (ref "VDIV_USB") (pin "1") (pinfunction "1_1") (pintype "passive"))
    )
    (net (code "39") (name "PA03_AREFA") (class "Default")
      (node (ref "C4") (pin "1") (pinfunction "1_1") (pintype "passive"))
      (node (ref "C5") (pin "+") (pinfunction "+_+") (pintype "passive"))
      (node (ref "IC2") (pin "4") (pinfunction "PA3/EIC/REF/AIN1_4") (pintype "bidirectional"))
      (node (ref "IOH") (pin "8") (pinfunction "8_8") (pintype "passive"))
      (node (ref "TP_AREF") (pin "X") (pinfunction "TESTP_X") (pintype "passive"))
    )
    (net (code "40") (name "PA04_AIN4") (class "Default")
      (node (ref "AD") (pin "4") (pinfunction "4_4") (pintype "passive"))
      (node (ref "IC2") (pin "9") (pinfunction "PA4/EIC/REF/AIN4/SCOM0PAD0/TC0_9") (pintype "bidirectional"))
      (node (ref "TP_A3") (pin "X") (pinfunction "TESTP_X") (pintype "passive"))
    )
    (net (code "41") (name "PA05_AIN5") (class "Default")
      (node (ref "AD") (pin "5") (pinfunction "5_5") (pintype "passive"))
      (node (ref "IC2") (pin "10") (pinfunction "PA5/EIC/AIN5/SCOM0PAD1/TC0_10") (pintype "bidirectional"))
      (node (ref "TP_A4") (pin "X") (pinfunction "TESTP_X") (pintype "passive"))
    )
    (net (code "42") (name "PA06_AIN6") (class "Default")
      (node (ref "IC2") (pin "11") (pinfunction "PA6/EIC/AIN6/SCOM0PAD2/TC1_11") (pintype "bidirectional"))
      (node (ref "IOH") (pin "1") (pinfunction "1_1") (pintype "passive"))
    )
    (net (code "43") (name "PA6_RFID_SHD") (class "Default")
      (node (ref "IC6") (pin "14") (pinfunction "SHD_14") (pintype "input"))
    )
    (net (code "44") (name "PA7_RF_SWTICH") (class "Default")
      (node (ref "IC2") (pin "12") (pinfunction "PA7/EIC/AIN7/SCOM0PAD3/TC1_12") (pintype "bidirectional"))
      (node (ref "IOH") (pin "2") (pinfunction "2_2") (pintype "passive"))
      (node (ref "K2") (pin "1") (pinfunction "A_1") (pintype "passive"))
      (node (ref "K2") (pin "3") (pinfunction "A_3") (pintype "passive"))
      (node (ref "TP_9") (pin "X") (pinfunction "TESTP_X") (pintype "passive"))
      (node (ref "U2") (pin "2") (pinfunction "A_2") (pintype "bidirectional"))
    )
    (net (code "45") (name "PA08_TCC0-W0_PA8") (class "Default")
      (node (ref "IC2") (pin "13") (pinfunction "PA8/I2C/AIN16/SCOM2PAD0+/TC0_13") (pintype "bidirectional"))
      (node (ref "IOL") (pin "3") (pinfunction "3_3") (pintype "passive"))
      (node (ref "TP_2") (pin "X") (pinfunction "TESTP_X") (pintype "passive"))
    )
    (net (code "46") (name "PA09_TCC0-W1_PA9") (class "Default")
      (node (ref "IC2") (pin "14") (pinfunction "PA9/I2C/EIC/AIN17/SCOM2PAD1+/TC0_14") (pintype "bidirectional"))
      (node (ref "IOL") (pin "4") (pinfunction "4_4") (pintype "passive"))
      (node (ref "TP_3") (pin "X") (pinfunction "TESTP_X") (pintype "passive"))
    )
    (net (code "47") (name "PA10_MISO") (class "Default")
      (node (ref "TP_12") (pin "X") (pinfunction "TESTP_X") (pintype "passive"))
    )
    (net (code "48") (name "PA10_TCC0-W2_PA10") (class "Default")
      (node (ref "IC2") (pin "15") (pinfunction "PA10/EIC/AIN18/SCOM2PAD2+/TC1_15") (pintype "bidirectional"))
      (node (ref "IOL") (pin "2") (pinfunction "2_2") (pintype "passive"))
      (node (ref "TP_1") (pin "X") (pinfunction "TESTP_X") (pintype "passive"))
    )
    (net (code "49") (name "PA11_TCC0-W3_PA11") (class "Default")
      (node (ref "IC2") (pin "16") (pinfunction "PA11/EIC/AIN19/SCOM2PAD3+/TC1_16") (pintype "bidirectional"))
      (node (ref "IOL") (pin "1") (pinfunction "1_1") (pintype "passive"))
      (node (ref "TP_0") (pin "X") (pinfunction "TESTP_X") (pintype "passive"))
    )
    (net (code "50") (name "PA13") (class "Default")
      (node (ref "IC2") (pin "22") (pinfunction "PA13/I2C/EIC/SCOM2PAD1+/TC2_22") (pintype "bidirectional"))
      (node (ref "IOL") (pin "8") (pinfunction "8_8") (pintype "passive"))
    )
    (net (code "51") (name "PA14_TCC0-W4") (class "Default")
      (node (ref "IC2") (pin "23") (pinfunction "PA14/XIN/EIC/SCOM2PAD2+/TC3_23") (pintype "bidirectional"))
      (node (ref "IOL") (pin "5") (pinfunction "5_5") (pintype "passive"))
      (node (ref "TP_4") (pin "X") (pinfunction "TESTP_X") (pintype "passive"))
    )
    (net (code "52") (name "PA15_TCC0-W5") (class "Default")
      (node (ref "IC2") (pin "24") (pinfunction "PA15/XOUT/EIC/SCOM2PAD3+/TC3_24") (pintype "bidirectional"))
      (node (ref "IOL") (pin "6") (pinfunction "6_6") (pintype "passive"))
      (node (ref "TP_5") (pin "X") (pinfunction "TESTP_X") (pintype "passive"))
    )
    (net (code "53") (name "PA16_MOSI") (class "Default")
      (node (ref "IC2") (pin "25") (pinfunction "PA16/I2C/EIC/SCOM1PAD0+/TC2_25") (pintype "bidirectional"))
      (node (ref "IOH") (pin "4") (pinfunction "4_4") (pintype "passive"))
      (node (ref "TP_MOSI") (pin "X") (pinfunction "TESTP_X") (pintype "passive"))
    )
    (net (code "54") (name "PA17_SCK") (class "Default")
      (node (ref "IC2") (pin "26") (pinfunction "PA17/I2C/EIC/SCOM1PAD1+/TC2_26") (pintype "bidirectional"))
      (node (ref "IOH") (pin "6") (pinfunction "6_6") (pintype "passive"))
      (node (ref "TP_SCK") (pin "X") (pinfunction "TESTP_X") (pintype "passive"))
    )
    (net (code "55") (name "PA18_SS") (class "Default")
      (node (ref "IC2") (pin "27") (pinfunction "PA18/EIC/SCOM1PAD2+/TC3_27") (pintype "bidirectional"))
      (node (ref "IOH") (pin "3") (pinfunction "3_3") (pintype "passive"))
      (node (ref "TP_10") (pin "X") (pinfunction "TESTP_X") (pintype "passive"))
    )
    (net (code "56") (name "PA19_MISO") (class "Default")
      (node (ref "IC2") (pin "28") (pinfunction "PA19/EIC/SCOM1PAD3+/TC3_28") (pintype "bidirectional"))
      (node (ref "IOH") (pin "5") (pinfunction "5_5") (pintype "passive"))
    )
    (net (code "57") (name "PA20_TCC0-W6") (class "Default")
      (node (ref "IC2") (pin "29") (pinfunction "PA20/EIC/SCOM5PAD2+_29") (pintype "bidirectional"))
      (node (ref "IOL") (pin "7") (pinfunction "7_7") (pintype "passive"))
      (node (ref "TP_6") (pin "X") (pinfunction "TESTP_X") (pintype "passive"))
    )
    (net (code "58") (name "PA21_INT&SDCS") (class "Default")
      (node (ref "IC2") (pin "30") (pinfunction "PA21/EIC/SCOM5PAD3+_30") (pintype "bidirectional"))
      (node (ref "IC5") (pin "7") (pinfunction "~{INT1/CLK}_7") (pintype "output"))
      (node (ref "R9") (pin "1") (pinfunction "1_1") (pintype "passive"))
      (node (ref "U$4") (pin "1") (pinfunction "CS_1") (pintype "input"))
    )
    (net (code "59") (name "PA22_SDA") (class "Default")
      (node (ref "IC2") (pin "31") (pinfunction "PA22/I2C/EIC/SCOM5PAD0+/TC4_31") (pintype "bidirectional"))
      (node (ref "IC5") (pin "5") (pinfunction "SDA_5") (pintype "bidirectional"))
      (node (ref "IOH") (pin "9") (pinfunction "9_9") (pintype "passive"))
      (node (ref "R13") (pin "1") (pinfunction "1_1") (pintype "passive"))
      (node (ref "TP_SDA") (pin "X") (pinfunction "TESTP_X") (pintype "passive"))
    )
    (net (code "60") (name "PA23_SCL") (class "Default")
      (node (ref "IC2") (pin "32") (pinfunction "PA23/I2C/EIC/SCOM5PAD1+/TC4_32") (pintype "bidirectional"))
      (node (ref "IC5") (pin "6") (pinfunction "SCL_6") (pintype "bidirectional"))
      (node (ref "IOH") (pin "10") (pinfunction "10_10") (pintype "passive"))
      (node (ref "R12") (pin "1") (pinfunction "1_1") (pintype "passive"))
      (node (ref "TP_SCL") (pin "X") (pinfunction "TESTP_X") (pintype "passive"))
    )
    (net (code "61") (name "PA27_TX_LED") (class "Default")
      (node (ref "IC2") (pin "39") (pinfunction "PA27/EIC_39") (pintype "bidirectional"))
      (node (ref "R6") (pin "2") (pinfunction "2_2") (pintype "passive"))
    )
    (net (code "62") (name "PA28_2FETS") (class "Default")
      (node (ref "IC2") (pin "41") (pinfunction "PA28/EIC_41") (pintype "bidirectional"))
      (node (ref "T1_VDIV") (pin "1") (pinfunction "G_1") (pintype "passive"))
      (node (ref "T_SD") (pin "1") (pinfunction "G_1") (pintype "passive"))
    )
    (net (code "63") (name "PA30_SWCLK") (class "Default")
      (node (ref "IC2") (pin "45") (pinfunction "PA30/EIC/SCOM1PAD2/TC1_45") (pintype "bidirectional"))
      (node (ref "R4") (pin "1") (pinfunction "1_1") (pintype "passive"))
    )
    (net (code "64") (name "PA31_SWDIO") (class "Default")
      (node (ref "IC2") (pin "46") (pinfunction "PA31/EIC/SCOM1PAD3/TC1_46") (pintype "bidirectional"))
      (node (ref "R3") (pin "2") (pinfunction "2_2") (pintype "passive"))
    )
    (net (code "65") (name "PB02") (class "Default")
      (node (ref "AD") (pin "6") (pinfunction "6_6") (pintype "passive"))
      (node (ref "IC2") (pin "47") (pinfunction "PB2/EIC/AIN10/SCOM5PAD0_47") (pintype "bidirectional"))
    )
    (net (code "66") (name "PB03_RFIDIN") (class "Default")
      (node (ref "IC2") (pin "48") (pinfunction "PB3/EIC/AIN11/SCOM5PAD1_48") (pintype "bidirectional"))
      (node (ref "IC6") (pin "13") (pinfunction "DMOD_OUT_13") (pintype "output"))
    )
    (net (code "67") (name "PB08_AIN2") (class "Default")
      (node (ref "AD") (pin "2") (pinfunction "2_2") (pintype "passive"))
      (node (ref "IC2") (pin "7") (pinfunction "PB8/EIC/AIN2/SCOM4PAD0/TC4_7") (pintype "bidirectional"))
      (node (ref "TP_A1") (pin "X") (pinfunction "TESTP_X") (pintype "passive"))
    )
    (net (code "68") (name "PB09_AIN3") (class "Default")
      (node (ref "AD") (pin "3") (pinfunction "3_3") (pintype "passive"))
      (node (ref "IC2") (pin "8") (pinfunction "PB9/EIC/AIN3/SCOM4PAD1//TC4_8") (pintype "bidirectional"))
      (node (ref "TP_A2") (pin "X") (pinfunction "TESTP_X") (pintype "passive"))
    )
    (net (code "69") (name "PB10_S4_SPI_MOSI") (class "Default")
      (node (ref "IC2") (pin "19") (pinfunction "PB10/EIC/SCOM4PAD2/TC5_19") (pintype "bidirectional"))
      (node (ref "ICSP") (pin "4") (pinfunction "4_4") (pintype "passive"))
      (node (ref "U$4") (pin "2") (pinfunction "DATA_IN_2") (pintype "input"))
    )
    (net (code "70") (name "PB11_S4_SPI_SCK") (class "Default")
      (node (ref "IC2") (pin "20") (pinfunction "PB11/EIC/SCOM4PAD3/TC5_20") (pintype "bidirectional"))
      (node (ref "ICSP") (pin "3") (pinfunction "3_3") (pintype "passive"))
      (node (ref "U$4") (pin "5") (pinfunction "SCLK_5") (pintype "input"))
    )
    (net (code "71") (name "PB12_S4_SPI_MISO") (class "Default")
      (node (ref "IC2") (pin "21") (pinfunction "PA12/I2C/EIC/SCOM2PAD0+/TC2_21") (pintype "bidirectional"))
      (node (ref "ICSP") (pin "1") (pinfunction "1_1") (pintype "passive"))
      (node (ref "U$4") (pin "7") (pinfunction "DATA_OUT_7") (pintype "output"))
    )
    (net (code "72") (name "PB22_DEBUG_TX") (class "Default")
      (node (ref "IC2") (pin "37") (pinfunction "PB22/EIC/SCOM5PAD2_37") (pintype "bidirectional"))
      (node (ref "J1") (pin "2") (pinfunction "S_2") (pintype "passive"))
    )
    (net (code "73") (name "PB23_DEBUG_RX") (class "Default")
      (node (ref "IC2") (pin "38") (pinfunction "PB23/EIC/SCOM5PAD3_38") (pintype "bidirectional"))
      (node (ref "J1") (pin "1") (pinfunction "S_1") (pintype "passive"))
    )
    (net (code "74") (name "PWRIN_1") (class "Default")
      (node (ref "U$6") (pin "P$1") (pinfunction "S_P$1") (pintype "passive"))
      (node (ref "U$6") (pin "P$2") (pinfunction "S_P$2") (pintype "passive"))
      (node (ref "U$9") (pin "P$3") (pinfunction "P_P$3") (pintype "passive"))
    )
    (net (code "75") (name "RESET") (class "Default")
      (node (ref "CN2") (pin "10") (pinfunction "10_10") (pintype "passive"))
      (node (ref "D2") (pin "A") (pinfunction "A_A") (pintype "passive"))
      (node (ref "ICSP") (pin "5") (pinfunction "5_5") (pintype "passive"))
      (node (ref "POWER") (pin "3") (pinfunction "3_3") (pintype "passive"))
      (node (ref "R1") (pin "1") (pinfunction "1_1") (pintype "passive"))
      (node (ref "R2") (pin "2") (pinfunction "2_2") (pintype "passive"))
      (node (ref "RESET") (pin "3") (pinfunction "3_3") (pintype "passive"))
      (node (ref "RESET") (pin "4") (pinfunction "4_4") (pintype "passive"))
      (node (ref "TP_RESET") (pin "X") (pinfunction "TESTP_X") (pintype "passive"))
    )
    (net (code "76") (name "SWCLK") (class "Default")
      (node (ref "CN2") (pin "4") (pinfunction "4_4") (pintype "passive"))
      (node (ref "R4") (pin "2") (pinfunction "2_2") (pintype "passive"))
    )
    (net (code "77") (name "SWDIO") (class "Default")
      (node (ref "CN2") (pin "2") (pinfunction "2_2") (pintype "passive"))
      (node (ref "R3") (pin "1") (pinfunction "1_1") (pintype "passive"))
    )
    (net (code "78") (name "TARGET_RESET") (class "Default")
      (node (ref "C8") (pin "1") (pinfunction "1_1") (pintype "passive"))
      (node (ref "IC2") (pin "40") (pinfunction "RESETN_40") (pintype "bidirectional"))
      (node (ref "R2") (pin "1") (pinfunction "1_1") (pintype "passive"))
    )
    (net (code "79") (name "TARGET_USB_N") (class "Default")
      (node (ref "IC2") (pin "33") (pinfunction "PA24/EIC/SCOM3PAD2+/TC5_33") (pintype "bidirectional"))
      (node (ref "U$5") (pin "D-") (pinfunction "D-_D-") (pintype "bidirectional"))
      (node (ref "Z6") (pin "1") (pinfunction "1_1") (pintype "passive"))
    )
    (net (code "80") (name "TARGET_USB_P") (class "Default")
      (node (ref "IC2") (pin "34") (pinfunction "PA25/EIC/SCOM3PAD3+/TC5_34") (pintype "bidirectional"))
      (node (ref "U$5") (pin "D+") (pinfunction "D+_D+") (pintype "bidirectional"))
      (node (ref "Z5") (pin "1") (pinfunction "1_1") (pintype "passive"))
    )
    (net (code "81") (name "VDDCORE") (class "Default")
      (node (ref "C19") (pin "1") (pinfunction "1_1") (pintype "passive"))
      (node (ref "IC2") (pin "43") (pinfunction "VDDCORE1_43") (pintype "input"))
    )
    (net (code "82") (name "XUSB") (class "Default")
      (node (ref "C26") (pin "1") (pinfunction "1_1") (pintype "passive"))
      (node (ref "U$5") (pin "VBUS") (pinfunction "VBUS_VBUS") (pintype "bidirectional"))
      (node (ref "U$9") (pin "P$4") (pinfunction "P1_P$4") (pintype "passive"))
      (node (ref "VDIV_USB") (pin "2") (pinfunction "2_2") (pintype "passive"))
    )
    (net (code "83") (name "unconnected-(CN2-Pad6)") (class "Default")
      (node (ref "CN2") (pin "6") (pinfunction "6_6") (pintype "passive"))
    )
    (net (code "84") (name "unconnected-(CN2-Pad7)") (class "Default")
      (node (ref "CN2") (pin "7") (pinfunction "7_7") (pintype "passive"))
    )
    (net (code "85") (name "unconnected-(CN2-Pad8)") (class "Default")
      (node (ref "CN2") (pin "8") (pinfunction "8_8") (pintype "passive"))
    )
    (net (code "86") (name "unconnected-(IC6-RDY{slash}CLK-Pad2)") (class "Default")
      (node (ref "IC6") (pin "2") (pinfunction "RDY/CLK_2") (pintype "output"))
    )
    (net (code "87") (name "unconnected-(POWER-Pad1)") (class "Default")
      (node (ref "POWER") (pin "1") (pinfunction "1_1") (pintype "passive"))
    )
    (net (code "88") (name "unconnected-(TP_7-TESTP-PadX)") (class "Default")
      (node (ref "TP_7") (pin "X") (pinfunction "TESTP_X") (pintype "passive"))
    )
    (net (code "89") (name "unconnected-(TP_8-TESTP-PadX)") (class "Default")
      (node (ref "TP_8") (pin "X") (pinfunction "TESTP_X") (pintype "passive"))
    )
    (net (code "90") (name "unconnected-(U$4-CARD_DETECT-PadCD)") (class "Default")
      (node (ref "U$4") (pin "CD") (pinfunction "CARD_DETECT_CD") (pintype "passive"))
    )
    (net (code "91") (name "unconnected-(U$4-DAT1-Pad8)") (class "Default")
      (node (ref "U$4") (pin "8") (pinfunction "DAT1_8") (pintype "bidirectional"))
    )
    (net (code "92") (name "unconnected-(U$4-DAT2-Pad9)") (class "Default")
      (node (ref "U$4") (pin "9") (pinfunction "DAT2_9") (pintype "bidirectional"))
    )
    (net (code "93") (name "unconnected-(U$4-WRITE_PROTECT-PadWP)") (class "Default")
      (node (ref "U$4") (pin "WP") (pinfunction "WRITE_PROTECT_WP") (pintype "passive"))
    )
    (net (code "94") (name "unconnected-(U$5-PadID)") (class "Default")
      (node (ref "U$5") (pin "ID") (pinfunction "ID_ID") (pintype "bidirectional"))
    )
    (net (code "95") (name "unconnected-(U$9-O1-PadP$2)") (class "Default")
      (node (ref "U$9") (pin "P$2") (pinfunction "O1_P$2") (pintype "passive"))
    )
    (net (code "96") (name "unconnected-(U$9-S-PadP$5)") (class "Default")
      (node (ref "U$9") (pin "P$5") (pinfunction "S_P$5") (pintype "passive"))
    )
    (net (code "97") (name "unconnected-(U2-NC-Pad1)") (class "Default")
      (node (ref "U2") (pin "1") (pinfunction "NC_1") (pintype "bidirectional"))
    )
  )
)
